# LVDS_IFCB.net
KiCad netlist of a schematic drawn in Altium Designer
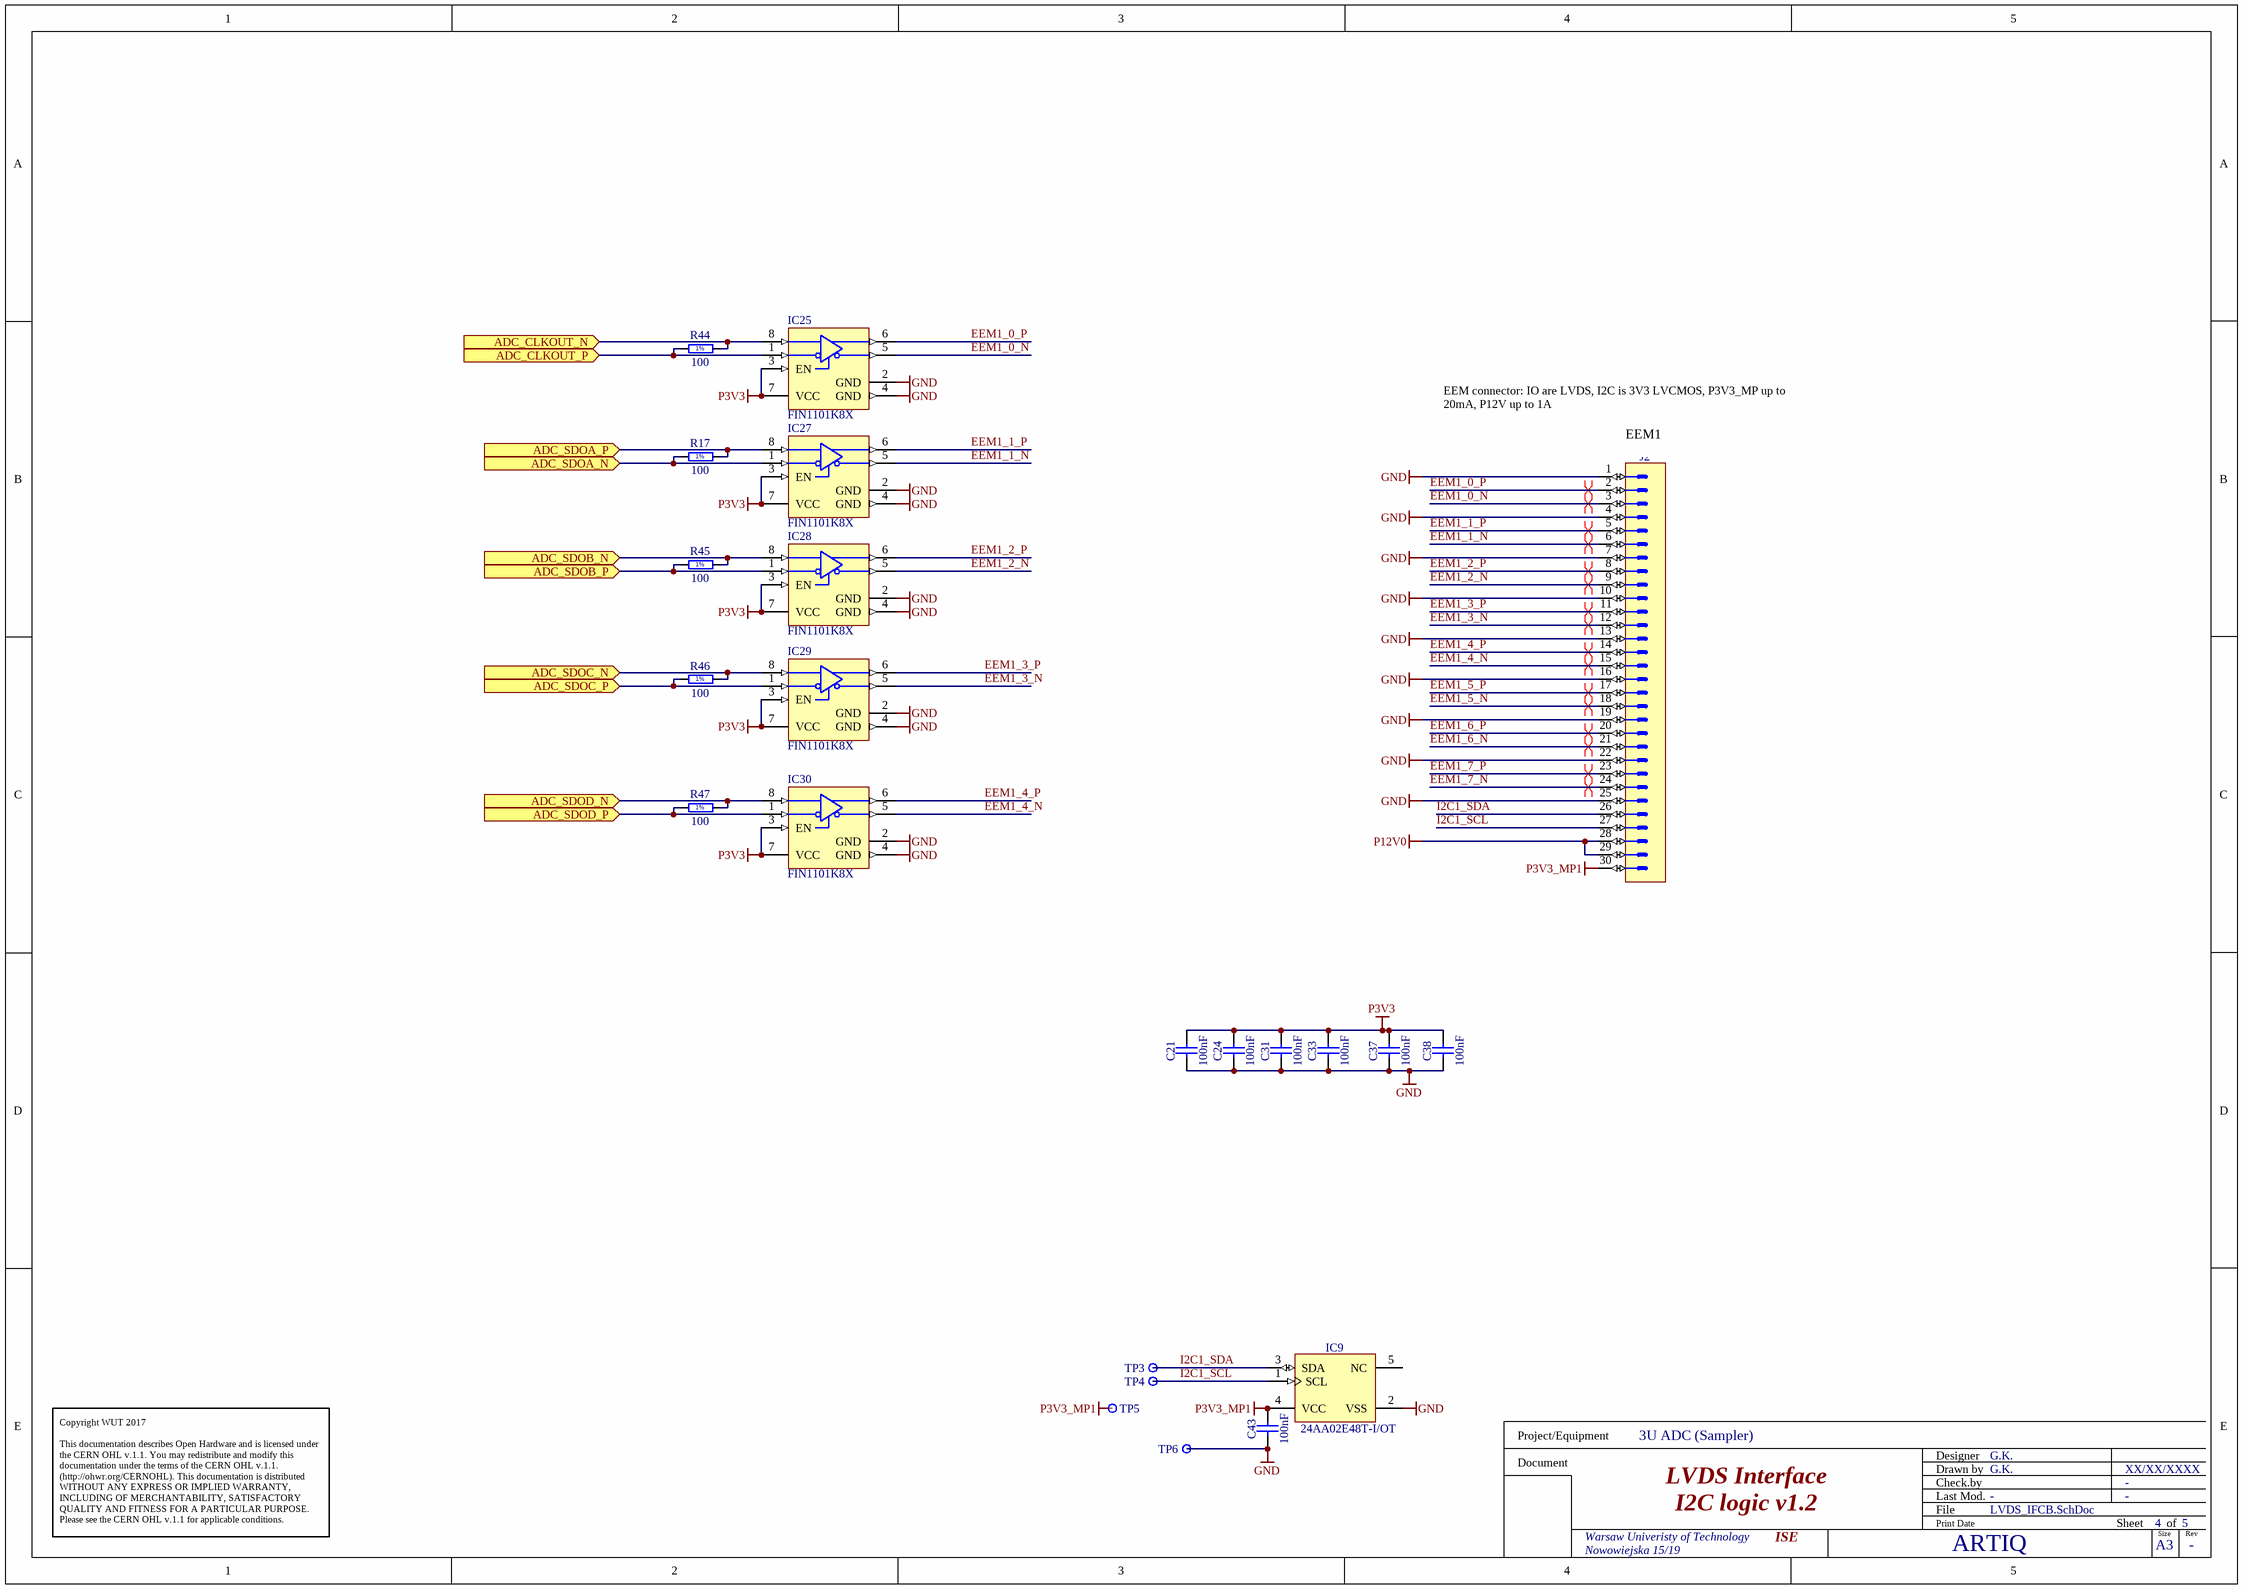
[diagram p0: LVDS_IFCB.SchDoc]

(export (version "E")
  (design (tool "Eeschema 10.0.6"))
  (components
    (comp (ref "C21")
      (value "100nF")
      (footprint "CAPC1005X55N")
      (description "Non-polarised capacitor")
      (fields
        (field (name "PART NUMBER") "CC0402_100NF_16V_10%_X5R")
        (field (name "VOLTAGE") "16V")
        (field (name "AUTHOR") "CERN DEM JLC")
      )
      (libsource (lib "Capacitors") (part "Capacitor - non polarized"))
    )
    (comp (ref "C24")
      (value "100nF")
      (footprint "CAPC1005X55N")
      (description "Non-polarised capacitor")
      (fields
        (field (name "PART NUMBER") "CC0402_100NF_16V_10%_X5R")
        (field (name "VOLTAGE") "16V")
        (field (name "AUTHOR") "CERN DEM JLC")
      )
      (libsource (lib "Capacitors") (part "Capacitor - non polarized"))
    )
    (comp (ref "C31")
      (value "100nF")
      (footprint "CAPC1005X55N")
      (description "Non-polarised capacitor")
      (fields
        (field (name "PART NUMBER") "CC0402_100NF_16V_10%_X5R")
        (field (name "VOLTAGE") "16V")
        (field (name "AUTHOR") "CERN DEM JLC")
      )
      (libsource (lib "Capacitors") (part "Capacitor - non polarized"))
    )
    (comp (ref "C33")
      (value "100nF")
      (footprint "CAPC1005X55N")
      (description "Non-polarised capacitor")
      (fields
        (field (name "PART NUMBER") "CC0402_100NF_16V_10%_X5R")
        (field (name "VOLTAGE") "16V")
        (field (name "AUTHOR") "CERN DEM JLC")
      )
      (libsource (lib "Capacitors") (part "Capacitor - non polarized"))
    )
    (comp (ref "C37")
      (value "100nF")
      (footprint "CAPC1005X55N")
      (description "Non-polarised capacitor")
      (fields
        (field (name "PART NUMBER") "CC0402_100NF_16V_10%_X5R")
        (field (name "VOLTAGE") "16V")
        (field (name "AUTHOR") "CERN DEM JLC")
      )
      (libsource (lib "Capacitors") (part "Capacitor - non polarized"))
    )
    (comp (ref "C38")
      (value "100nF")
      (footprint "CAPC1005X55N")
      (description "Non-polarised capacitor")
      (fields
        (field (name "PART NUMBER") "CC0402_100NF_16V_10%_X5R")
        (field (name "VOLTAGE") "16V")
        (field (name "AUTHOR") "CERN DEM JLC")
      )
      (libsource (lib "Capacitors") (part "Capacitor - non polarized"))
    )
    (comp (ref "C43")
      (value "100nF")
      (footprint "CAPC1005X55N")
      (description "Non-polarised capacitor")
      (fields
        (field (name "PART NUMBER") "CC0402_100NF_16V_10%_X5R")
        (field (name "VOLTAGE") "16V")
        (field (name "AUTHOR") "CERN DEM JLC")
      )
      (libsource (lib "Capacitors") (part "Capacitor - non polarized"))
    )
    (comp (ref "IC9")
      (value "24AA02E48T-I/OT")
      (footprint "SOT95P280X145-5N")
      (description "1.7V-5.5V, 2K I2C Serial EEPROM With EUI-48 Node Identity")
      (fields (field (name "MANUFACTURER") "MICROCHIP TECHNOLOGY") (field (name "AUTHOR") "CERN DEM MR"))
      (libsource (lib "ICs And Semiconductors") (part "24AA02E48T-I/OT"))
    )
    (comp (ref "IC25")
      (value "FIN1101K8X")
      (footprint "SOP50P310X90-8N")
      (description "LVDS Single Port High Speed Repeater")
      (fields (field (name "MANUFACTURER") "FAIRCHILD SEMICONDUCTOR") (field (name "AUTHOR") "CERN DEM JLC"))
      (libsource (lib "ICs And Semiconductors") (part "FIN1101K8X"))
    )
    (comp (ref "IC27")
      (value "FIN1101K8X")
      (footprint "SOP50P310X90-8N")
      (description "LVDS Single Port High Speed Repeater")
      (fields (field (name "MANUFACTURER") "FAIRCHILD SEMICONDUCTOR") (field (name "AUTHOR") "CERN DEM JLC"))
      (libsource (lib "ICs And Semiconductors") (part "FIN1101K8X"))
    )
    (comp (ref "IC28")
      (value "FIN1101K8X")
      (footprint "SOP50P310X90-8N")
      (description "LVDS Single Port High Speed Repeater")
      (fields (field (name "MANUFACTURER") "FAIRCHILD SEMICONDUCTOR") (field (name "AUTHOR") "CERN DEM JLC"))
      (libsource (lib "ICs And Semiconductors") (part "FIN1101K8X"))
    )
    (comp (ref "IC29")
      (value "FIN1101K8X")
      (footprint "SOP50P310X90-8N")
      (description "LVDS Single Port High Speed Repeater")
      (fields (field (name "MANUFACTURER") "FAIRCHILD SEMICONDUCTOR") (field (name "AUTHOR") "CERN DEM JLC"))
      (libsource (lib "ICs And Semiconductors") (part "FIN1101K8X"))
    )
    (comp (ref "IC30")
      (value "FIN1101K8X")
      (footprint "SOP50P310X90-8N")
      (description "LVDS Single Port High Speed Repeater")
      (fields (field (name "MANUFACTURER") "FAIRCHILD SEMICONDUCTOR") (field (name "AUTHOR") "CERN DEM JLC"))
      (libsource (lib "ICs And Semiconductors") (part "FIN1101K8X"))
    )
    (comp (ref "J2")
      (value "~")
      (footprint "3M_N2530-6002RB")
      (description "Connector 30 Male")
      (fields
        (field (name "PART NUMBER") "3M_N2530-6002RB")
        (field (name "MANUFACTURER") "3M")
        (field (name "AUTHOR") "CERN DEM JLC")
      )
      (libsource (lib "Connectors") (part "Connector 30 Male"))
    )
    (comp (ref "R17")
      (value "100")
      (footprint "RESC1005X40N")
      (description "Resistor - 1%")
      (fields
        (field (name "PART NUMBER") "R0402_100R_1%_0.1W_100PPM")
        (field (name "POWER") "0.1W")
        (field (name "AUTHOR") "CERN DEM JLC")
      )
      (libsource (lib "Resistors") (part "Resistor - 1%"))
    )
    (comp (ref "R44")
      (value "100")
      (footprint "RESC1005X40N")
      (description "Resistor - 1%")
      (fields
        (field (name "PART NUMBER") "R0402_100R_1%_0.1W_100PPM")
        (field (name "POWER") "0.1W")
        (field (name "AUTHOR") "CERN DEM JLC")
      )
      (libsource (lib "Resistors") (part "Resistor - 1%"))
    )
    (comp (ref "R45")
      (value "100")
      (footprint "RESC1005X40N")
      (description "Resistor - 1%")
      (fields
        (field (name "PART NUMBER") "R0402_100R_1%_0.1W_100PPM")
        (field (name "POWER") "0.1W")
        (field (name "AUTHOR") "CERN DEM JLC")
      )
      (libsource (lib "Resistors") (part "Resistor - 1%"))
    )
    (comp (ref "R46")
      (value "100")
      (footprint "RESC1005X40N")
      (description "Resistor - 1%")
      (fields
        (field (name "PART NUMBER") "R0402_100R_1%_0.1W_100PPM")
        (field (name "POWER") "0.1W")
        (field (name "AUTHOR") "CERN DEM JLC")
      )
      (libsource (lib "Resistors") (part "Resistor - 1%"))
    )
    (comp (ref "R47")
      (value "100")
      (footprint "RESC1005X40N")
      (description "Resistor - 1%")
      (fields
        (field (name "PART NUMBER") "R0402_100R_1%_0.1W_100PPM")
        (field (name "POWER") "0.1W")
        (field (name "AUTHOR") "CERN DEM JLC")
      )
      (libsource (lib "Resistors") (part "Resistor - 1%"))
    )
    (comp (ref "TP3")
      (value "Test Point")
      (footprint "TPS127")
      (fields (field (name "PART NUMBER") "SMD_PAD_1.27X1.27MM") (field (name "AUTHOR") "CERN DEM JLC"))
      (libsource (lib "Eletro-mechanical") (part "Test Point"))
    )
    (comp (ref "TP4")
      (value "Test Point")
      (footprint "TPS127")
      (fields (field (name "PART NUMBER") "SMD_PAD_1.27X1.27MM") (field (name "AUTHOR") "CERN DEM JLC"))
      (libsource (lib "Eletro-mechanical") (part "Test Point"))
    )
    (comp (ref "TP5")
      (value "Test Point")
      (footprint "TPS127")
      (fields (field (name "PART NUMBER") "SMD_PAD_1.27X1.27MM") (field (name "AUTHOR") "CERN DEM JLC"))
      (libsource (lib "Eletro-mechanical") (part "Test Point"))
    )
    (comp (ref "TP6")
      (value "Test Point")
      (footprint "TPS127")
      (fields (field (name "PART NUMBER") "SMD_PAD_1.27X1.27MM") (field (name "AUTHOR") "CERN DEM JLC"))
      (libsource (lib "Eletro-mechanical") (part "Test Point"))
    )
  )
  (nets
    (net (code "1") (name "/ADC_CLKOUT_N") (class "Default")
      (node (ref "IC25") (pin "8") (pinfunction "RIN+_8") (pintype "input"))
      (node (ref "R44") (pin "2") (pinfunction "2_2") (pintype "passive"))
    )
    (net (code "2") (name "/ADC_CLKOUT_P") (class "Default")
      (node (ref "IC25") (pin "1") (pinfunction "RIN-_1") (pintype "input"))
      (node (ref "R44") (pin "1") (pinfunction "1_1") (pintype "passive"))
    )
    (net (code "3") (name "/ADC_SDOA_N") (class "Default")
      (node (ref "IC27") (pin "1") (pinfunction "RIN-_1") (pintype "input"))
      (node (ref "R17") (pin "1") (pinfunction "1_1") (pintype "passive"))
    )
    (net (code "4") (name "/ADC_SDOA_P") (class "Default")
      (node (ref "IC27") (pin "8") (pinfunction "RIN+_8") (pintype "input"))
      (node (ref "R17") (pin "2") (pinfunction "2_2") (pintype "passive"))
    )
    (net (code "5") (name "/ADC_SDOB_N") (class "Default")
      (node (ref "IC28") (pin "8") (pinfunction "RIN+_8") (pintype "input"))
      (node (ref "R45") (pin "2") (pinfunction "2_2") (pintype "passive"))
    )
    (net (code "6") (name "/ADC_SDOB_P") (class "Default")
      (node (ref "IC28") (pin "1") (pinfunction "RIN-_1") (pintype "input"))
      (node (ref "R45") (pin "1") (pinfunction "1_1") (pintype "passive"))
    )
    (net (code "7") (name "/ADC_SDOC_N") (class "Default")
      (node (ref "IC29") (pin "8") (pinfunction "RIN+_8") (pintype "input"))
      (node (ref "R46") (pin "2") (pinfunction "2_2") (pintype "passive"))
    )
    (net (code "8") (name "/ADC_SDOC_P") (class "Default")
      (node (ref "IC29") (pin "1") (pinfunction "RIN-_1") (pintype "input"))
      (node (ref "R46") (pin "1") (pinfunction "1_1") (pintype "passive"))
    )
    (net (code "9") (name "/ADC_SDOD_N") (class "Default")
      (node (ref "IC30") (pin "8") (pinfunction "RIN+_8") (pintype "input"))
      (node (ref "R47") (pin "2") (pinfunction "2_2") (pintype "passive"))
    )
    (net (code "10") (name "/ADC_SDOD_P") (class "Default")
      (node (ref "IC30") (pin "1") (pinfunction "RIN-_1") (pintype "input"))
      (node (ref "R47") (pin "1") (pinfunction "1_1") (pintype "passive"))
    )
    (net (code "11") (name "/EEM1_0_N") (class "Default")
      (node (ref "IC25") (pin "5") (pinfunction "DOUT-_5") (pintype "output"))
      (node (ref "J2") (pin "3") (pinfunction "3_3") (pintype "bidirectional"))
    )
    (net (code "12") (name "/EEM1_0_P") (class "Default")
      (node (ref "IC25") (pin "6") (pinfunction "DOUT+_6") (pintype "output"))
      (node (ref "J2") (pin "2") (pinfunction "2_2") (pintype "bidirectional"))
    )
    (net (code "13") (name "/EEM1_1_N") (class "Default")
      (node (ref "IC27") (pin "5") (pinfunction "DOUT-_5") (pintype "output"))
      (node (ref "J2") (pin "6") (pinfunction "6_6") (pintype "bidirectional"))
    )
    (net (code "14") (name "/EEM1_1_P") (class "Default")
      (node (ref "IC27") (pin "6") (pinfunction "DOUT+_6") (pintype "output"))
      (node (ref "J2") (pin "5") (pinfunction "5_5") (pintype "bidirectional"))
    )
    (net (code "15") (name "/EEM1_2_N") (class "Default")
      (node (ref "IC28") (pin "5") (pinfunction "DOUT-_5") (pintype "output"))
      (node (ref "J2") (pin "9") (pinfunction "9_9") (pintype "bidirectional"))
    )
    (net (code "16") (name "/EEM1_2_P") (class "Default")
      (node (ref "IC28") (pin "6") (pinfunction "DOUT+_6") (pintype "output"))
      (node (ref "J2") (pin "8") (pinfunction "8_8") (pintype "bidirectional"))
    )
    (net (code "17") (name "/EEM1_3_N") (class "Default")
      (node (ref "IC29") (pin "5") (pinfunction "DOUT-_5") (pintype "output"))
      (node (ref "J2") (pin "12") (pinfunction "12_12") (pintype "bidirectional"))
    )
    (net (code "18") (name "/EEM1_3_P") (class "Default")
      (node (ref "IC29") (pin "6") (pinfunction "DOUT+_6") (pintype "output"))
      (node (ref "J2") (pin "11") (pinfunction "11_11") (pintype "bidirectional"))
    )
    (net (code "19") (name "/EEM1_4_N") (class "Default")
      (node (ref "IC30") (pin "5") (pinfunction "DOUT-_5") (pintype "output"))
      (node (ref "J2") (pin "15") (pinfunction "15_15") (pintype "bidirectional"))
    )
    (net (code "20") (name "/EEM1_4_P") (class "Default")
      (node (ref "IC30") (pin "6") (pinfunction "DOUT+_6") (pintype "output"))
      (node (ref "J2") (pin "14") (pinfunction "14_14") (pintype "bidirectional"))
    )
    (net (code "21") (name "/EEM1_5_N") (class "Default")
      (node (ref "J2") (pin "18") (pinfunction "18_18") (pintype "bidirectional"))
    )
    (net (code "22") (name "/EEM1_5_P") (class "Default")
      (node (ref "J2") (pin "17") (pinfunction "17_17") (pintype "bidirectional"))
    )
    (net (code "23") (name "/EEM1_6_N") (class "Default")
      (node (ref "J2") (pin "21") (pinfunction "21_21") (pintype "bidirectional"))
    )
    (net (code "24") (name "/EEM1_6_P") (class "Default")
      (node (ref "J2") (pin "20") (pinfunction "20_20") (pintype "bidirectional"))
    )
    (net (code "25") (name "/EEM1_7_N") (class "Default")
      (node (ref "J2") (pin "24") (pinfunction "24_24") (pintype "bidirectional"))
    )
    (net (code "26") (name "/EEM1_7_P") (class "Default")
      (node (ref "J2") (pin "23") (pinfunction "23_23") (pintype "bidirectional"))
    )
    (net (code "27") (name "/I2C1_SCL") (class "Default")
      (node (ref "IC9") (pin "1") (pinfunction "SCL_1") (pintype "input"))
      (node (ref "J2") (pin "27") (pinfunction "27_27") (pintype "bidirectional"))
      (node (ref "TP4") (pin "1") (pinfunction "1_1") (pintype "bidirectional"))
    )
    (net (code "28") (name "/I2C1_SDA") (class "Default")
      (node (ref "IC9") (pin "3") (pinfunction "SDA_3") (pintype "bidirectional"))
      (node (ref "J2") (pin "26") (pinfunction "26_26") (pintype "bidirectional"))
      (node (ref "TP3") (pin "1") (pinfunction "1_1") (pintype "bidirectional"))
    )
    (net (code "29") (name "GND") (class "Default")
      (node (ref "C21") (pin "1") (pinfunction "1_1") (pintype "passive"))
      (node (ref "C24") (pin "1") (pinfunction "1_1") (pintype "passive"))
      (node (ref "C31") (pin "1") (pinfunction "1_1") (pintype "passive"))
      (node (ref "C33") (pin "1") (pinfunction "1_1") (pintype "passive"))
      (node (ref "C37") (pin "1") (pinfunction "1_1") (pintype "passive"))
      (node (ref "C38") (pin "1") (pinfunction "1_1") (pintype "passive"))
      (node (ref "C43") (pin "1") (pinfunction "1_1") (pintype "passive"))
      (node (ref "IC25") (pin "2") (pinfunction "GND_2") (pintype "power_in"))
      (node (ref "IC25") (pin "4") (pinfunction "GND_4") (pintype "output"))
      (node (ref "IC27") (pin "2") (pinfunction "GND_2") (pintype "power_in"))
      (node (ref "IC27") (pin "4") (pinfunction "GND_4") (pintype "output"))
      (node (ref "IC28") (pin "2") (pinfunction "GND_2") (pintype "power_in"))
      (node (ref "IC28") (pin "4") (pinfunction "GND_4") (pintype "output"))
      (node (ref "IC29") (pin "2") (pinfunction "GND_2") (pintype "power_in"))
      (node (ref "IC29") (pin "4") (pinfunction "GND_4") (pintype "output"))
      (node (ref "IC30") (pin "2") (pinfunction "GND_2") (pintype "power_in"))
      (node (ref "IC30") (pin "4") (pinfunction "GND_4") (pintype "output"))
      (node (ref "IC9") (pin "2") (pinfunction "VSS_2") (pintype "power_in"))
      (node (ref "J2") (pin "1") (pinfunction "1_1") (pintype "bidirectional"))
      (node (ref "J2") (pin "10") (pinfunction "10_10") (pintype "bidirectional"))
      (node (ref "J2") (pin "13") (pinfunction "13_13") (pintype "bidirectional"))
      (node (ref "J2") (pin "16") (pinfunction "16_16") (pintype "bidirectional"))
      (node (ref "J2") (pin "19") (pinfunction "19_19") (pintype "bidirectional"))
      (node (ref "J2") (pin "22") (pinfunction "22_22") (pintype "bidirectional"))
      (node (ref "J2") (pin "25") (pinfunction "25_25") (pintype "bidirectional"))
      (node (ref "J2") (pin "4") (pinfunction "4_4") (pintype "bidirectional"))
      (node (ref "J2") (pin "7") (pinfunction "7_7") (pintype "bidirectional"))
      (node (ref "TP6") (pin "1") (pinfunction "1_1") (pintype "bidirectional"))
    )
    (net (code "30") (name "P3V3") (class "Default")
      (node (ref "C21") (pin "2") (pinfunction "2_2") (pintype "passive"))
      (node (ref "C24") (pin "2") (pinfunction "2_2") (pintype "passive"))
      (node (ref "C31") (pin "2") (pinfunction "2_2") (pintype "passive"))
      (node (ref "C33") (pin "2") (pinfunction "2_2") (pintype "passive"))
      (node (ref "C37") (pin "2") (pinfunction "2_2") (pintype "passive"))
      (node (ref "C38") (pin "2") (pinfunction "2_2") (pintype "passive"))
      (node (ref "IC25") (pin "3") (pinfunction "EN_3") (pintype "input"))
      (node (ref "IC25") (pin "7") (pinfunction "VCC_7") (pintype "power_in"))
      (node (ref "IC27") (pin "3") (pinfunction "EN_3") (pintype "input"))
      (node (ref "IC27") (pin "7") (pinfunction "VCC_7") (pintype "power_in"))
      (node (ref "IC28") (pin "3") (pinfunction "EN_3") (pintype "input"))
      (node (ref "IC28") (pin "7") (pinfunction "VCC_7") (pintype "power_in"))
      (node (ref "IC29") (pin "3") (pinfunction "EN_3") (pintype "input"))
      (node (ref "IC29") (pin "7") (pinfunction "VCC_7") (pintype "power_in"))
      (node (ref "IC30") (pin "3") (pinfunction "EN_3") (pintype "input"))
      (node (ref "IC30") (pin "7") (pinfunction "VCC_7") (pintype "power_in"))
    )
    (net (code "31") (name "P3V3_MP1") (class "Default")
      (node (ref "C43") (pin "2") (pinfunction "2_2") (pintype "passive"))
      (node (ref "IC9") (pin "4") (pinfunction "VCC_4") (pintype "power_in"))
      (node (ref "J2") (pin "30") (pinfunction "30_30") (pintype "bidirectional"))
      (node (ref "TP5") (pin "1") (pinfunction "1_1") (pintype "bidirectional"))
    )
    (net (code "32") (name "P12V0") (class "Default")
      (node (ref "J2") (pin "28") (pinfunction "28_28") (pintype "bidirectional"))
      (node (ref "J2") (pin "29") (pinfunction "29_29") (pintype "bidirectional"))
    )
    (net (code "33") (name "unconnected-(IC9-NC-Pad5)") (class "Default")
      (node (ref "IC9") (pin "5") (pinfunction "NC_5") (pintype "passive"))
    )
  )
)
